# TCC.net
KiCad netlist of a schematic drawn in EAGLE
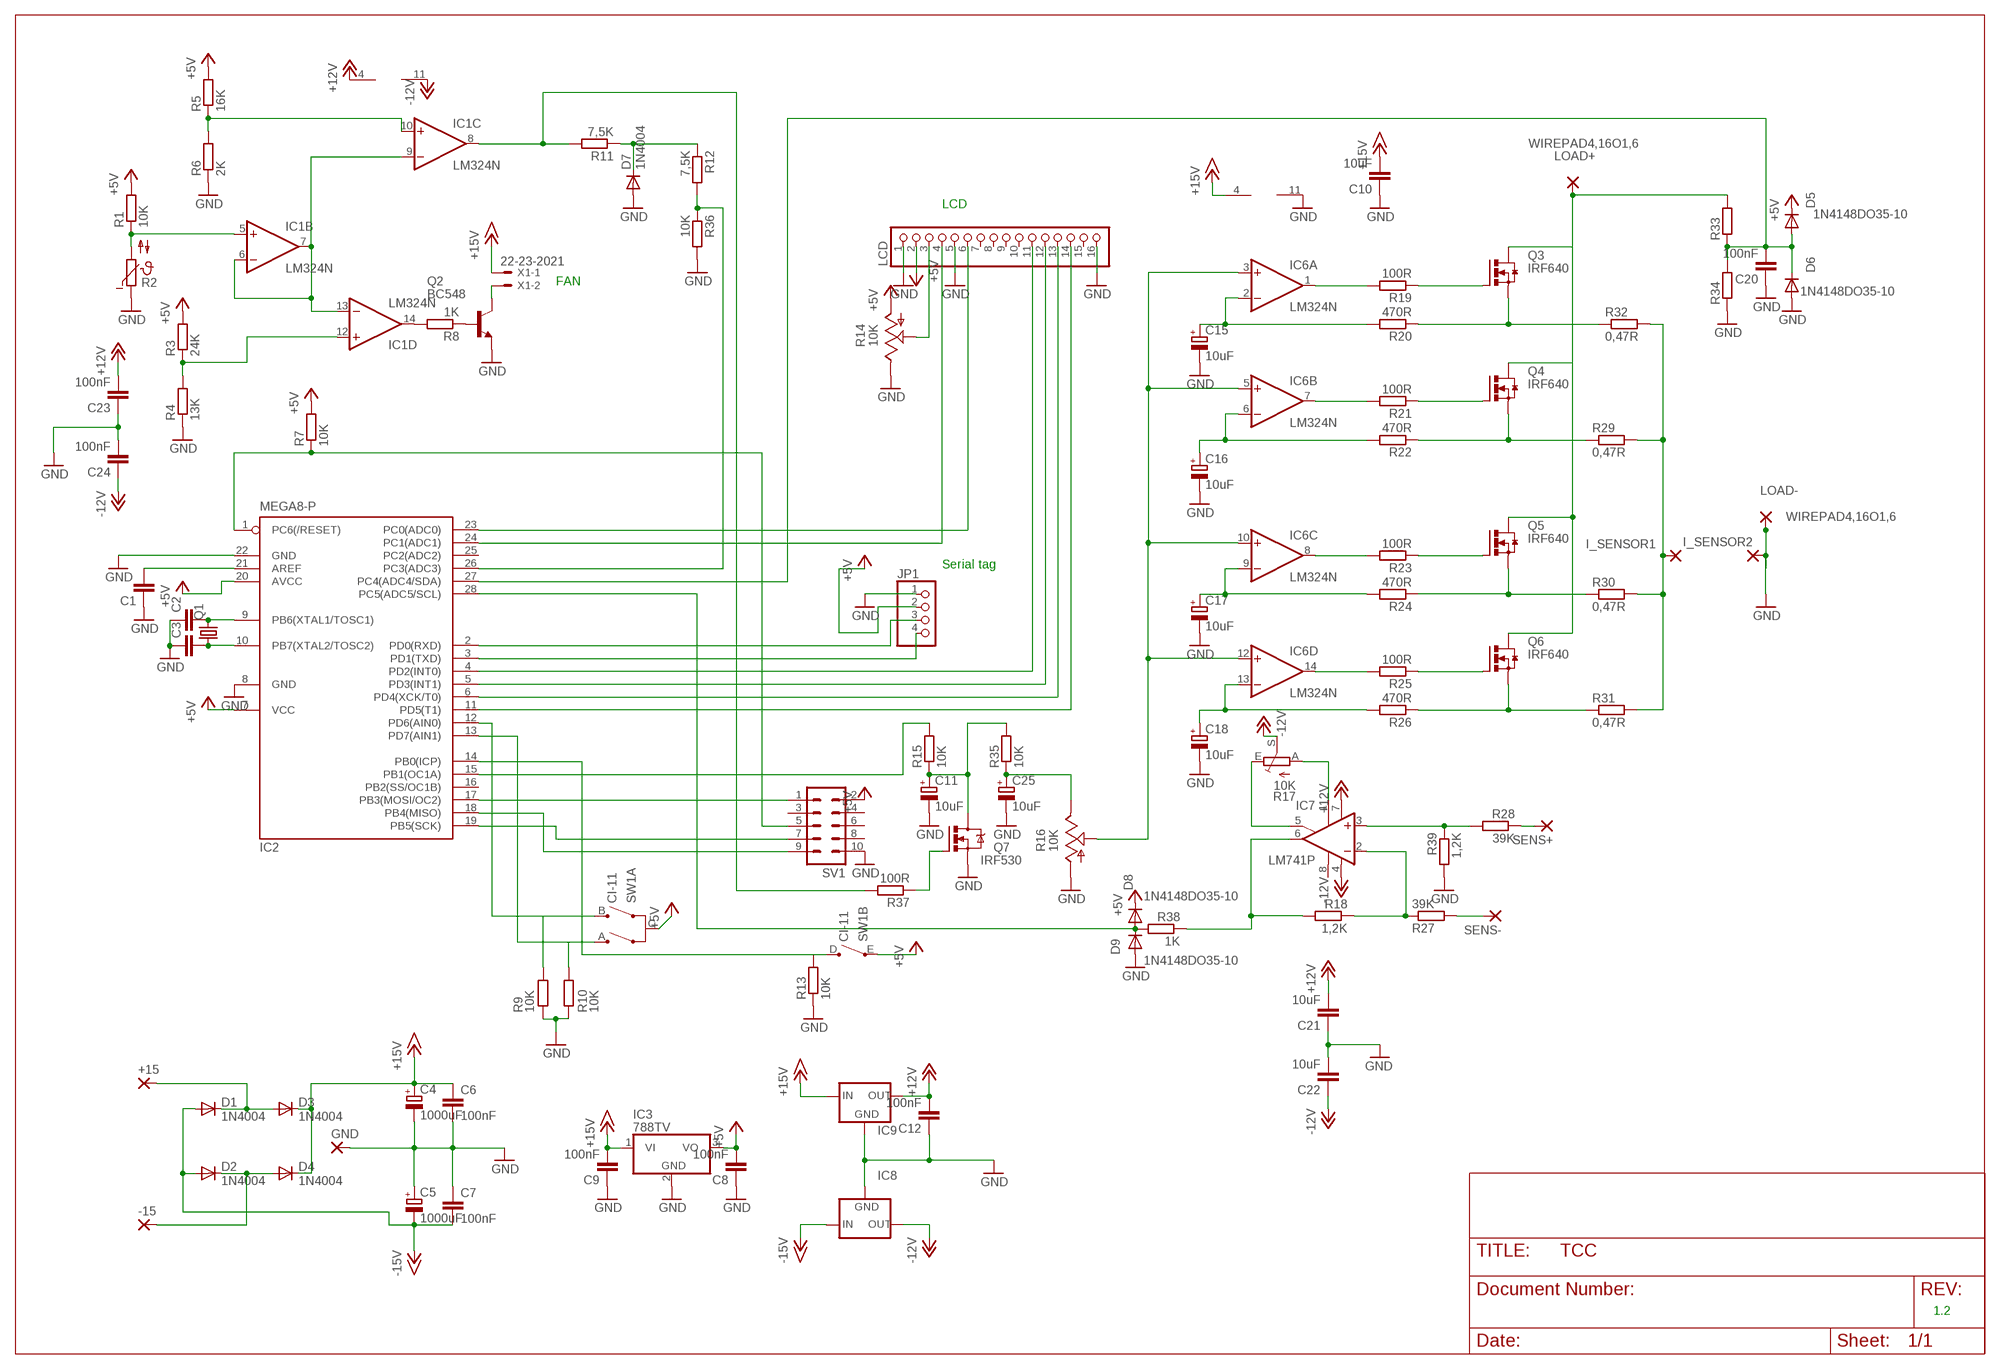
[diagram p0: schematic, sheet 1]

(export (version "E")
  (design (tool "Eeschema 10.0.6"))
  (components
    (comp (ref "+15")
      (value "2,54/0,9")
      (footprint "eagle-import:2,54_0,9")
      (libsource (lib "eagle-import") (part "2,54/0,9"))
    )
    (comp (ref "-15")
      (value "2,54/0,9")
      (footprint "eagle-import:2,54_0,9")
      (libsource (lib "eagle-import") (part "2,54/0,9"))
    )
    (comp (ref "C1")
      (value "C5/2.5")
      (footprint "eagle-import:C5B2.5")
      (libsource (lib "eagle-import") (part "C5/2.5"))
    )
    (comp (ref "C2")
      (value "C5/2.5")
      (footprint "eagle-import:C5B2.5")
      (libsource (lib "eagle-import") (part "C5/2.5"))
    )
    (comp (ref "C3")
      (value "C5/2.5")
      (footprint "eagle-import:C5B2.5")
      (libsource (lib "eagle-import") (part "C5/2.5"))
    )
    (comp (ref "C4")
      (value "1000uF")
      (footprint "eagle-import:E3,5-10")
      (libsource (lib "eagle-import") (part "CPOL-EUE3.5-10"))
    )
    (comp (ref "C5")
      (value "1000uF")
      (footprint "eagle-import:E3,5-10")
      (libsource (lib "eagle-import") (part "CPOL-EUE3.5-10"))
    )
    (comp (ref "C6")
      (value "100nF")
      (footprint "eagle-import:C050-025X075")
      (libsource (lib "eagle-import") (part "C-EU050-025X075"))
    )
    (comp (ref "C7")
      (value "100nF")
      (footprint "eagle-import:C050-025X075")
      (libsource (lib "eagle-import") (part "C-EU050-025X075"))
    )
    (comp (ref "C8")
      (value "100nF")
      (footprint "eagle-import:C5B2.5")
      (libsource (lib "eagle-import") (part "C5/2.5"))
    )
    (comp (ref "C9")
      (value "100nF")
      (footprint "eagle-import:C5B2.5")
      (libsource (lib "eagle-import") (part "C5/2.5"))
    )
    (comp (ref "C10")
      (value "10uF")
      (footprint "eagle-import:C5B2.5")
      (libsource (lib "eagle-import") (part "C5/2.5"))
    )
    (comp (ref "C11")
      (value "10uF")
      (footprint "eagle-import:E2,5-6E")
      (libsource (lib "eagle-import") (part "CPOL-EUE2,5-6E"))
    )
    (comp (ref "C12")
      (value "100nF")
      (footprint "eagle-import:C5B2.5")
      (libsource (lib "eagle-import") (part "C5/2.5"))
    )
    (comp (ref "C15")
      (value "10uF")
      (footprint "eagle-import:E2,5-6E")
      (libsource (lib "eagle-import") (part "CPOL-EUE2,5-6E"))
    )
    (comp (ref "C16")
      (value "10uF")
      (footprint "eagle-import:E2,5-6E")
      (libsource (lib "eagle-import") (part "CPOL-EUE2,5-6E"))
    )
    (comp (ref "C17")
      (value "10uF")
      (footprint "eagle-import:E2,5-6E")
      (libsource (lib "eagle-import") (part "CPOL-EUE2,5-6E"))
    )
    (comp (ref "C18")
      (value "10uF")
      (footprint "eagle-import:E2,5-6E")
      (libsource (lib "eagle-import") (part "CPOL-EUE2,5-6E"))
    )
    (comp (ref "C20")
      (value "100nF")
      (footprint "eagle-import:C5B2.5")
      (libsource (lib "eagle-import") (part "C5/2.5"))
    )
    (comp (ref "C21")
      (value "10uF")
      (footprint "eagle-import:C5B2.5")
      (libsource (lib "eagle-import") (part "C5/2.5"))
    )
    (comp (ref "C22")
      (value "10uF")
      (footprint "eagle-import:C5B2.5")
      (libsource (lib "eagle-import") (part "C5/2.5"))
    )
    (comp (ref "C23")
      (value "100nF")
      (footprint "eagle-import:C5B2.5")
      (libsource (lib "eagle-import") (part "C5/2.5"))
    )
    (comp (ref "C24")
      (value "100nF")
      (footprint "eagle-import:C5B2.5")
      (libsource (lib "eagle-import") (part "C5/2.5"))
    )
    (comp (ref "C25")
      (value "10uF")
      (footprint "eagle-import:E2,5-6E")
      (libsource (lib "eagle-import") (part "CPOL-EUE2,5-6E"))
    )
    (comp (ref "D1")
      (value "1N4004")
      (footprint "eagle-import:DO41-10")
      (libsource (lib "eagle-import") (part "1N4004"))
    )
    (comp (ref "D2")
      (value "1N4004")
      (footprint "eagle-import:DO41-10")
      (libsource (lib "eagle-import") (part "1N4004"))
    )
    (comp (ref "D3")
      (value "1N4004")
      (footprint "eagle-import:DO41-10")
      (libsource (lib "eagle-import") (part "1N4004"))
    )
    (comp (ref "D4")
      (value "1N4004")
      (footprint "eagle-import:DO41-10")
      (libsource (lib "eagle-import") (part "1N4004"))
    )
    (comp (ref "D5")
      (value "1N4148DO35-10")
      (footprint "eagle-import:DO35-10")
      (libsource (lib "eagle-import") (part "1N4148DO35-10"))
    )
    (comp (ref "D6")
      (value "1N4148DO35-10")
      (footprint "eagle-import:DO35-10")
      (libsource (lib "eagle-import") (part "1N4148DO35-10"))
    )
    (comp (ref "D7")
      (value "1N4004")
      (footprint "eagle-import:DO41-10")
      (libsource (lib "eagle-import") (part "1N4004"))
    )
    (comp (ref "D8")
      (value "1N4148DO35-10")
      (footprint "eagle-import:DO35-10")
      (libsource (lib "eagle-import") (part "1N4148DO35-10"))
    )
    (comp (ref "D9")
      (value "1N4148DO35-10")
      (footprint "eagle-import:DO35-10")
      (libsource (lib "eagle-import") (part "1N4148DO35-10"))
    )
    (comp (ref "GND")
      (value "2,54/0,9")
      (footprint "eagle-import:2,54_0,9")
      (libsource (lib "eagle-import") (part "2,54/0,9"))
    )
    (comp (ref "IC1")
      (value "LM324N")
      (footprint "eagle-import:DIL14")
      (libsource (lib "eagle-import") (part "LM324N"))
    )
    (comp (ref "IC2")
      (value "MEGA8-P")
      (footprint "eagle-import:DIL28-3")
      (libsource (lib "eagle-import") (part "MEGA8-P"))
    )
    (comp (ref "IC3")
      (value "788TV")
      (footprint "eagle-import:TO220V")
      (libsource (lib "eagle-import") (part "78TV8"))
    )
    (comp (ref "IC6")
      (value "LM324N")
      (footprint "eagle-import:DIL14")
      (libsource (lib "eagle-import") (part "LM324N"))
    )
    (comp (ref "IC7")
      (value "LM741P")
      (footprint "eagle-import:DIL08")
      (libsource (lib "eagle-import") (part "741PLM"))
    )
    (comp (ref "IC8")
      (value "79XXS")
      (footprint "eagle-import:79XXS")
      (libsource (lib "eagle-import") (part "79XXS"))
    )
    (comp (ref "IC9")
      (value "78XXS")
      (footprint "eagle-import:78XXS")
      (libsource (lib "eagle-import") (part "78XXS"))
    )
    (comp (ref "I_SENSOR1")
      (value "3,17/1,3")
      (footprint "eagle-import:3,17_1,3")
      (libsource (lib "eagle-import") (part "3,17/1,3"))
    )
    (comp (ref "I_SENSOR2")
      (value "3,17/1,3")
      (footprint "eagle-import:3,17_1,3")
      (libsource (lib "eagle-import") (part "3,17/1,3"))
    )
    (comp (ref "JP1")
      (value "PINHD-1X4")
      (footprint "eagle-import:1X04")
      (libsource (lib "eagle-import") (part "PINHD-1X4"))
    )
    (comp (ref "LCD")
      (value "PINHD-1X16")
      (footprint "eagle-import:1X16")
      (libsource (lib "eagle-import") (part "PINHD-1X16"))
    )
    (comp (ref "LOAD+")
      (value "WIREPAD4,16O1,6")
      (footprint "eagle-import:4,16O1,6")
      (libsource (lib "eagle-import") (part "WIREPAD4,16O1,6"))
    )
    (comp (ref "LOAD-")
      (value "WIREPAD4,16O1,6")
      (footprint "eagle-import:4,16O1,6")
      (libsource (lib "eagle-import") (part "WIREPAD4,16O1,6"))
    )
    (comp (ref "Q1")
      (value "CRYSTALHC49S")
      (footprint "eagle-import:HC49_S")
      (libsource (lib "eagle-import") (part "CRYSTALHC49S"))
    )
    (comp (ref "Q2")
      (value "BC548")
      (footprint "eagle-import:TO92-EBC")
      (libsource (lib "eagle-import") (part "BC548"))
    )
    (comp (ref "Q3")
      (value "IRF640")
      (footprint "eagle-import:TO220BH")
      (libsource (lib "eagle-import") (part "IRFI540NPBF"))
    )
    (comp (ref "Q4")
      (value "IRF640")
      (footprint "eagle-import:TO220BH")
      (libsource (lib "eagle-import") (part "IRFI540NPBF"))
    )
    (comp (ref "Q5")
      (value "IRF640")
      (footprint "eagle-import:TO220BH")
      (libsource (lib "eagle-import") (part "IRFI540NPBF"))
    )
    (comp (ref "Q6")
      (value "IRF640")
      (footprint "eagle-import:TO220BH")
      (libsource (lib "eagle-import") (part "IRFI540NPBF"))
    )
    (comp (ref "Q7")
      (value "IRF530")
      (footprint "eagle-import:TO220BV")
      (libsource (lib "eagle-import") (part "IRF530"))
    )
    (comp (ref "R1")
      (value "10K")
      (footprint "eagle-import:0207_12")
      (libsource (lib "eagle-import") (part "resistor_R-EU_0207/12"))
    )
    (comp (ref "R2")
      (value "NTC640")
      (footprint "eagle-import:P640")
      (libsource (lib "eagle-import") (part "NTC640"))
    )
    (comp (ref "R3")
      (value "24K")
      (footprint "eagle-import:0207_10")
      (libsource (lib "eagle-import") (part "resistor_R-EU_0207/10"))
    )
    (comp (ref "R4")
      (value "13K")
      (footprint "eagle-import:0204_7")
      (libsource (lib "eagle-import") (part "resistor_R-EU_0204/7"))
    )
    (comp (ref "R5")
      (value "16K")
      (footprint "eagle-import:0204_7")
      (libsource (lib "eagle-import") (part "resistor_R-EU_0204/7"))
    )
    (comp (ref "R6")
      (value "2K")
      (footprint "eagle-import:0204_7")
      (libsource (lib "eagle-import") (part "resistor_R-EU_0204/7"))
    )
    (comp (ref "R7")
      (value "10K")
      (footprint "eagle-import:0204_7")
      (libsource (lib "eagle-import") (part "resistor_R-EU_0204/7"))
    )
    (comp (ref "R8")
      (value "1K")
      (footprint "eagle-import:0204_7")
      (libsource (lib "eagle-import") (part "resistor_R-EU_0204/7"))
    )
    (comp (ref "R9")
      (value "10K")
      (footprint "eagle-import:0204_7")
      (libsource (lib "eagle-import") (part "R-EU_0204/7"))
    )
    (comp (ref "R10")
      (value "10K")
      (footprint "eagle-import:0204_7")
      (libsource (lib "eagle-import") (part "R-EU_0204/7"))
    )
    (comp (ref "R11")
      (value "7,5K")
      (footprint "eagle-import:0204_7")
      (libsource (lib "eagle-import") (part "resistor_R-EU_0204/7"))
    )
    (comp (ref "R12")
      (value "7,5K")
      (footprint "eagle-import:0204_7")
      (libsource (lib "eagle-import") (part "resistor_R-EU_0204/7"))
    )
    (comp (ref "R13")
      (value "10K")
      (footprint "eagle-import:0207_10")
      (libsource (lib "eagle-import") (part "R-EU_0207/10"))
    )
    (comp (ref "R14")
      (value "10K")
      (footprint "eagle-import:LI10@1")
      (libsource (lib "eagle-import") (part "TRIM_US-LI10"))
    )
    (comp (ref "R15")
      (value "10K")
      (footprint "eagle-import:0204_7")
      (libsource (lib "eagle-import") (part "resistor_R-EU_0204/7"))
    )
    (comp (ref "R16")
      (value "10K")
      (footprint "eagle-import:S64W")
      (libsource (lib "eagle-import") (part "TRIM_US-S64W"))
    )
    (comp (ref "R17")
      (value "10K")
      (footprint "eagle-import:LI10")
      (libsource (lib "eagle-import") (part "TRIM_EU-LI10"))
    )
    (comp (ref "R18")
      (value "1,2K")
      (footprint "eagle-import:0207_10")
      (libsource (lib "eagle-import") (part "R-EU_0207/10"))
    )
    (comp (ref "R19")
      (value "100R")
      (footprint "eagle-import:0207_10")
      (libsource (lib "eagle-import") (part "R-EU_0207/10"))
    )
    (comp (ref "R20")
      (value "470R")
      (footprint "eagle-import:0207_10")
      (libsource (lib "eagle-import") (part "R-EU_0207/10"))
    )
    (comp (ref "R21")
      (value "100R")
      (footprint "eagle-import:0207_15")
      (libsource (lib "eagle-import") (part "R-EU_0207/15"))
    )
    (comp (ref "R22")
      (value "470R")
      (footprint "eagle-import:0207_12")
      (libsource (lib "eagle-import") (part "R-EU_0207/12"))
    )
    (comp (ref "R23")
      (value "100R")
      (footprint "eagle-import:0207_15")
      (libsource (lib "eagle-import") (part "R-EU_0207/15"))
    )
    (comp (ref "R24")
      (value "470R")
      (footprint "eagle-import:0207_10")
      (libsource (lib "eagle-import") (part "R-EU_0207/10"))
    )
    (comp (ref "R25")
      (value "100R")
      (footprint "eagle-import:0207_10")
      (libsource (lib "eagle-import") (part "R-EU_0207/10"))
    )
    (comp (ref "R26")
      (value "470R")
      (footprint "eagle-import:0207_10")
      (libsource (lib "eagle-import") (part "R-EU_0207/10"))
    )
    (comp (ref "R27")
      (value "39K")
      (footprint "eagle-import:0207_10")
      (libsource (lib "eagle-import") (part "R-EU_0207/10"))
    )
    (comp (ref "R28")
      (value "39K")
      (footprint "eagle-import:0204_7")
      (libsource (lib "eagle-import") (part "R-EU_0204/7"))
    )
    (comp (ref "R29")
      (value "0,47R")
      (footprint "eagle-import:VTA56")
      (libsource (lib "eagle-import") (part "R-EU_VTA56"))
    )
    (comp (ref "R30")
      (value "0,47R")
      (footprint "eagle-import:VTA56")
      (libsource (lib "eagle-import") (part "R-EU_VTA56"))
    )
    (comp (ref "R31")
      (value "0,47R")
      (footprint "eagle-import:VTA56")
      (libsource (lib "eagle-import") (part "R-EU_VTA56"))
    )
    (comp (ref "R32")
      (value "0,47R")
      (footprint "eagle-import:VTA56")
      (libsource (lib "eagle-import") (part "R-EU_VTA56"))
    )
    (comp (ref "R33")
      (value "R-EU_0207/15")
      (footprint "eagle-import:0207_15")
      (libsource (lib "eagle-import") (part "R-EU_0207/15"))
    )
    (comp (ref "R34")
      (value "R-EU_0207/10")
      (footprint "eagle-import:0207_10")
      (libsource (lib "eagle-import") (part "R-EU_0207/10"))
    )
    (comp (ref "R35")
      (value "10K")
      (footprint "eagle-import:0204_7")
      (libsource (lib "eagle-import") (part "resistor_R-EU_0204/7"))
    )
    (comp (ref "R36")
      (value "10K")
      (footprint "eagle-import:0204_7")
      (libsource (lib "eagle-import") (part "resistor_R-EU_0204/7"))
    )
    (comp (ref "R37")
      (value "100R")
      (footprint "eagle-import:0204_7")
      (libsource (lib "eagle-import") (part "resistor_R-EU_0204/7"))
    )
    (comp (ref "R38")
      (value "1K")
      (footprint "eagle-import:0207_10")
      (libsource (lib "eagle-import") (part "R-EU_0207/10"))
    )
    (comp (ref "R39")
      (value "1,2K")
      (footprint "eagle-import:0207_10")
      (libsource (lib "eagle-import") (part "R-EU_0207/10"))
    )
    (comp (ref "SENS+")
      (value "2,54/1,1")
      (footprint "eagle-import:2,54_1,1")
      (libsource (lib "eagle-import") (part "2,54/1,1"))
    )
    (comp (ref "SENS-")
      (value "2,54/1,1")
      (footprint "eagle-import:2,54_1,1")
      (libsource (lib "eagle-import") (part "2,54/1,1"))
    )
    (comp (ref "SV1")
      (value "ML10")
      (footprint "eagle-import:ML10")
      (libsource (lib "eagle-import") (part "ML10"))
    )
    (comp (ref "SW1")
      (value "CI-11")
      (footprint "eagle-import:CI-11")
      (libsource (lib "eagle-import") (part "CI-11"))
    )
    (comp (ref "X1")
      (value "22-23-2021")
      (footprint "eagle-import:22-23-2021")
      (fields (field (name "MF") "MOLEX"))
      (libsource (lib "eagle-import") (part "22-23-2021"))
    )
  )
  (nets
    (net (code "1") (name "+5V") (class "Default")
      (node (ref "C8") (pin "2") (pinfunction "2_2") (pintype "passive"))
      (node (ref "D5") (pin "C") (pinfunction "C_C") (pintype "passive"))
      (node (ref "D8") (pin "C") (pinfunction "C_C") (pintype "passive"))
      (node (ref "IC2") (pin "20") (pinfunction "AVCC_20") (pintype "power_in"))
      (node (ref "IC2") (pin "7") (pinfunction "VCC_7") (pintype "power_in"))
      (node (ref "IC3") (pin "3") (pinfunction "VO_3") (pintype "passive"))
      (node (ref "JP1") (pin "2") (pinfunction "2_2") (pintype "passive"))
      (node (ref "LCD") (pin "2") (pinfunction "2_2") (pintype "passive"))
      (node (ref "R1") (pin "2") (pinfunction "2_2") (pintype "passive"))
      (node (ref "R14") (pin "A") (pinfunction "A_A") (pintype "passive"))
      (node (ref "R3") (pin "2") (pinfunction "2_2") (pintype "passive"))
      (node (ref "R5") (pin "2") (pinfunction "2_2") (pintype "passive"))
      (node (ref "R7") (pin "2") (pinfunction "2_2") (pintype "passive"))
      (node (ref "SV1") (pin "2") (pinfunction "2_2") (pintype "passive"))
      (node (ref "SW1") (pin "C") (pinfunction "C_C") (pintype "passive"))
      (node (ref "SW1") (pin "E") (pinfunction "E_E") (pintype "passive"))
    )
    (net (code "2") (name "+12V") (class "Default")
      (node (ref "C12") (pin "2") (pinfunction "2_2") (pintype "passive"))
      (node (ref "C21") (pin "2") (pinfunction "2_2") (pintype "passive"))
      (node (ref "C23") (pin "2") (pinfunction "2_2") (pintype "passive"))
      (node (ref "IC1") (pin "4") (pinfunction "V+_4") (pintype "power_in"))
      (node (ref "IC7") (pin "7") (pinfunction "V+_7") (pintype "power_in"))
      (node (ref "IC9") (pin "OUT") (pinfunction "OUT_OUT") (pintype "passive"))
    )
    (net (code "3") (name "+15V") (class "Default")
      (node (ref "C10") (pin "2") (pinfunction "2_2") (pintype "passive"))
      (node (ref "C4") (pin "+") (pinfunction "+_+") (pintype "passive"))
      (node (ref "C6") (pin "1") (pinfunction "1_1") (pintype "passive"))
      (node (ref "C9") (pin "2") (pinfunction "2_2") (pintype "passive"))
      (node (ref "D3") (pin "C") (pinfunction "C_C") (pintype "passive"))
      (node (ref "D4") (pin "C") (pinfunction "C_C") (pintype "passive"))
      (node (ref "IC3") (pin "1") (pinfunction "VI_1") (pintype "input"))
      (node (ref "IC6") (pin "4") (pinfunction "V+_4") (pintype "power_in"))
      (node (ref "IC9") (pin "IN") (pinfunction "IN_IN") (pintype "input"))
      (node (ref "X1") (pin "1") (pinfunction "S_1") (pintype "passive"))
    )
    (net (code "4") (name "-12V") (class "Default")
      (node (ref "C22") (pin "1") (pinfunction "1_1") (pintype "passive"))
      (node (ref "C24") (pin "1") (pinfunction "1_1") (pintype "passive"))
      (node (ref "IC1") (pin "11") (pinfunction "V-_11") (pintype "power_in"))
      (node (ref "IC7") (pin "4") (pinfunction "V-_4") (pintype "power_in"))
      (node (ref "IC8") (pin "OUT") (pinfunction "OUT_OUT") (pintype "passive"))
      (node (ref "R17") (pin "S") (pinfunction "S_S") (pintype "passive"))
    )
    (net (code "5") (name "-15V") (class "Default")
      (node (ref "C5") (pin "-") (pinfunction "-_-") (pintype "passive"))
      (node (ref "C7") (pin "2") (pinfunction "2_2") (pintype "passive"))
      (node (ref "D1") (pin "A") (pinfunction "A_A") (pintype "passive"))
      (node (ref "D2") (pin "A") (pinfunction "A_A") (pintype "passive"))
      (node (ref "IC8") (pin "IN") (pinfunction "IN_IN") (pintype "input"))
    )
    (net (code "6") (name "GND") (class "Default")
      (node (ref "C1") (pin "1") (pinfunction "1_1") (pintype "passive"))
      (node (ref "C10") (pin "1") (pinfunction "1_1") (pintype "passive"))
      (node (ref "C11") (pin "-") (pinfunction "-_-") (pintype "passive"))
      (node (ref "C12") (pin "1") (pinfunction "1_1") (pintype "passive"))
      (node (ref "C15") (pin "-") (pinfunction "-_-") (pintype "passive"))
      (node (ref "C16") (pin "-") (pinfunction "-_-") (pintype "passive"))
      (node (ref "C17") (pin "-") (pinfunction "-_-") (pintype "passive"))
      (node (ref "C18") (pin "-") (pinfunction "-_-") (pintype "passive"))
      (node (ref "C2") (pin "1") (pinfunction "1_1") (pintype "passive"))
      (node (ref "C20") (pin "1") (pinfunction "1_1") (pintype "passive"))
      (node (ref "C21") (pin "1") (pinfunction "1_1") (pintype "passive"))
      (node (ref "C22") (pin "2") (pinfunction "2_2") (pintype "passive"))
      (node (ref "C23") (pin "1") (pinfunction "1_1") (pintype "passive"))
      (node (ref "C24") (pin "2") (pinfunction "2_2") (pintype "passive"))
      (node (ref "C25") (pin "-") (pinfunction "-_-") (pintype "passive"))
      (node (ref "C3") (pin "1") (pinfunction "1_1") (pintype "passive"))
      (node (ref "C4") (pin "-") (pinfunction "-_-") (pintype "passive"))
      (node (ref "C5") (pin "+") (pinfunction "+_+") (pintype "passive"))
      (node (ref "C6") (pin "2") (pinfunction "2_2") (pintype "passive"))
      (node (ref "C7") (pin "1") (pinfunction "1_1") (pintype "passive"))
      (node (ref "C8") (pin "1") (pinfunction "1_1") (pintype "passive"))
      (node (ref "C9") (pin "1") (pinfunction "1_1") (pintype "passive"))
      (node (ref "D6") (pin "A") (pinfunction "A_A") (pintype "passive"))
      (node (ref "D7") (pin "A") (pinfunction "A_A") (pintype "passive"))
      (node (ref "D9") (pin "A") (pinfunction "A_A") (pintype "passive"))
      (node (ref "GND") (pin "1") (pinfunction "P_1") (pintype "passive"))
      (node (ref "IC2") (pin "22") (pinfunction "GND_22") (pintype "power_in"))
      (node (ref "IC2") (pin "8") (pinfunction "GND_8") (pintype "power_in"))
      (node (ref "IC3") (pin "2") (pinfunction "GND_2") (pintype "passive"))
      (node (ref "IC6") (pin "11") (pinfunction "V-_11") (pintype "power_in"))
      (node (ref "IC8") (pin "GND") (pinfunction "GND_GND") (pintype "input"))
      (node (ref "IC9") (pin "GND") (pinfunction "GND_GND") (pintype "input"))
      (node (ref "I_SENSOR2") (pin "1") (pinfunction "P_1") (pintype "passive"))
      (node (ref "JP1") (pin "1") (pinfunction "1_1") (pintype "passive"))
      (node (ref "LCD") (pin "1") (pinfunction "1_1") (pintype "passive"))
      (node (ref "LCD") (pin "16") (pinfunction "16_16") (pintype "passive"))
      (node (ref "LCD") (pin "5") (pinfunction "5_5") (pintype "passive"))
      (node (ref "LOAD-") (pin "1") (pinfunction "P_1") (pintype "passive"))
      (node (ref "Q2") (pin "E") (pinfunction "E_E") (pintype "passive"))
      (node (ref "Q7") (pin "S") (pinfunction "S_S") (pintype "passive"))
      (node (ref "R10") (pin "1") (pinfunction "1_1") (pintype "passive"))
      (node (ref "R13") (pin "1") (pinfunction "1_1") (pintype "passive"))
      (node (ref "R14") (pin "E") (pinfunction "E_E") (pintype "passive"))
      (node (ref "R16") (pin "A") (pinfunction "A_A") (pintype "passive"))
      (node (ref "R2") (pin "1") (pinfunction "1_1") (pintype "passive"))
      (node (ref "R34") (pin "1") (pinfunction "1_1") (pintype "passive"))
      (node (ref "R36") (pin "2") (pinfunction "2_2") (pintype "passive"))
      (node (ref "R39") (pin "2") (pinfunction "2_2") (pintype "passive"))
      (node (ref "R4") (pin "1") (pinfunction "1_1") (pintype "passive"))
      (node (ref "R6") (pin "1") (pinfunction "1_1") (pintype "passive"))
      (node (ref "R9") (pin "1") (pinfunction "1_1") (pintype "passive"))
      (node (ref "SV1") (pin "10") (pinfunction "10_10") (pintype "passive"))
    )
    (net (code "7") (name "Net-(+15-P)") (class "Default")
      (node (ref "+15") (pin "1") (pinfunction "P_1") (pintype "passive"))
      (node (ref "D1") (pin "C") (pinfunction "C_C") (pintype "passive"))
      (node (ref "D3") (pin "A") (pinfunction "A_A") (pintype "passive"))
    )
    (net (code "8") (name "Net-(-15-P)") (class "Default")
      (node (ref "-15") (pin "1") (pinfunction "P_1") (pintype "passive"))
      (node (ref "D2") (pin "C") (pinfunction "C_C") (pintype "passive"))
      (node (ref "D4") (pin "A") (pinfunction "A_A") (pintype "passive"))
    )
    (net (code "9") (name "Net-(C11-Pad+)") (class "Default")
      (node (ref "C11") (pin "+") (pinfunction "+_+") (pintype "passive"))
      (node (ref "Q7") (pin "D") (pinfunction "D_D") (pintype "passive"))
      (node (ref "R15") (pin "1") (pinfunction "1_1") (pintype "passive"))
      (node (ref "R35") (pin "2") (pinfunction "2_2") (pintype "passive"))
    )
    (net (code "10") (name "Net-(C25-Pad+)") (class "Default")
      (node (ref "C25") (pin "+") (pinfunction "+_+") (pintype "passive"))
      (node (ref "R16") (pin "E") (pinfunction "E_E") (pintype "passive"))
      (node (ref "R35") (pin "1") (pinfunction "1_1") (pintype "passive"))
    )
    (net (code "11") (name "Net-(D7-PadC)") (class "Default")
      (node (ref "D7") (pin "C") (pinfunction "C_C") (pintype "passive"))
      (node (ref "R11") (pin "1") (pinfunction "1_1") (pintype "passive"))
      (node (ref "R12") (pin "1") (pinfunction "1_1") (pintype "passive"))
    )
    (net (code "12") (name "Net-(IC1B-+IN)") (class "Default")
      (node (ref "IC1") (pin "5") (pinfunction "+IN_5") (pintype "input"))
      (node (ref "R1") (pin "1") (pinfunction "1_1") (pintype "passive"))
      (node (ref "R2") (pin "2") (pinfunction "2_2") (pintype "passive"))
    )
    (net (code "13") (name "Net-(IC1B--IN)") (class "Default")
      (node (ref "IC1") (pin "13") (pinfunction "-IN_13") (pintype "input"))
      (node (ref "IC1") (pin "6") (pinfunction "-IN_6") (pintype "input"))
      (node (ref "IC1") (pin "7") (pinfunction "OUT_7") (pintype "output"))
      (node (ref "IC1") (pin "9") (pinfunction "-IN_9") (pintype "input"))
    )
    (net (code "14") (name "Net-(IC1C-+IN)") (class "Default")
      (node (ref "IC1") (pin "10") (pinfunction "+IN_10") (pintype "input"))
      (node (ref "R5") (pin "1") (pinfunction "1_1") (pintype "passive"))
      (node (ref "R6") (pin "2") (pinfunction "2_2") (pintype "passive"))
    )
    (net (code "15") (name "Net-(IC1C-OUT)") (class "Default")
      (node (ref "IC1") (pin "8") (pinfunction "OUT_8") (pintype "output"))
      (node (ref "R11") (pin "2") (pinfunction "2_2") (pintype "passive"))
      (node (ref "R37") (pin "2") (pinfunction "2_2") (pintype "passive"))
    )
    (net (code "16") (name "Net-(IC1D-+IN)") (class "Default")
      (node (ref "IC1") (pin "12") (pinfunction "+IN_12") (pintype "input"))
      (node (ref "R3") (pin "1") (pinfunction "1_1") (pintype "passive"))
      (node (ref "R4") (pin "2") (pinfunction "2_2") (pintype "passive"))
    )
    (net (code "17") (name "Net-(IC1D-OUT)") (class "Default")
      (node (ref "IC1") (pin "14") (pinfunction "OUT_14") (pintype "output"))
      (node (ref "R8") (pin "2") (pinfunction "2_2") (pintype "passive"))
    )
    (net (code "18") (name "Net-(IC2-AREF)") (class "Default")
      (node (ref "C1") (pin "2") (pinfunction "2_2") (pintype "passive"))
      (node (ref "IC2") (pin "21") (pinfunction "AREF_21") (pintype "passive"))
    )
    (net (code "19") (name "Net-(IC2-PB0(ICP))") (class "Default")
      (node (ref "IC2") (pin "14") (pinfunction "PB0(ICP)_14") (pintype "bidirectional"))
      (node (ref "R13") (pin "2") (pinfunction "2_2") (pintype "passive"))
      (node (ref "SW1") (pin "D") (pinfunction "D_D") (pintype "passive"))
    )
    (net (code "20") (name "Net-(IC2-PB1(OC1A))") (class "Default")
      (node (ref "IC2") (pin "15") (pinfunction "PB1(OC1A)_15") (pintype "bidirectional"))
      (node (ref "R15") (pin "2") (pinfunction "2_2") (pintype "passive"))
    )
    (net (code "21") (name "Net-(IC2-PB3(MOSI{slash}OC2))") (class "Default")
      (node (ref "IC2") (pin "17") (pinfunction "PB3(MOSI/OC2)_17") (pintype "bidirectional"))
      (node (ref "SV1") (pin "1") (pinfunction "1_1") (pintype "passive"))
    )
    (net (code "22") (name "Net-(IC2-PB4(MISO))") (class "Default")
      (node (ref "IC2") (pin "18") (pinfunction "PB4(MISO)_18") (pintype "bidirectional"))
      (node (ref "SV1") (pin "9") (pinfunction "9_9") (pintype "passive"))
    )
    (net (code "23") (name "Net-(IC2-PB5(SCK))") (class "Default")
      (node (ref "IC2") (pin "19") (pinfunction "PB5(SCK)_19") (pintype "bidirectional"))
      (node (ref "SV1") (pin "7") (pinfunction "7_7") (pintype "passive"))
    )
    (net (code "24") (name "Net-(IC2-PB6(XTAL1{slash}TOSC1))") (class "Default")
      (node (ref "C2") (pin "2") (pinfunction "2_2") (pintype "passive"))
      (node (ref "IC2") (pin "9") (pinfunction "PB6(XTAL1/TOSC1)_9") (pintype "bidirectional"))
      (node (ref "Q1") (pin "2") (pinfunction "2_2") (pintype "passive"))
    )
    (net (code "25") (name "Net-(IC2-PB7(XTAL2{slash}TOSC2))") (class "Default")
      (node (ref "C3") (pin "2") (pinfunction "2_2") (pintype "passive"))
      (node (ref "IC2") (pin "10") (pinfunction "PB7(XTAL2/TOSC2)_10") (pintype "bidirectional"))
      (node (ref "Q1") (pin "1") (pinfunction "1_1") (pintype "passive"))
    )
    (net (code "26") (name "Net-(IC2-PC0(ADC0))") (class "Default")
      (node (ref "IC2") (pin "23") (pinfunction "PC0(ADC0)_23") (pintype "bidirectional"))
      (node (ref "LCD") (pin "6") (pinfunction "6_6") (pintype "passive"))
    )
    (net (code "27") (name "Net-(IC2-PC1(ADC1))") (class "Default")
      (node (ref "IC2") (pin "24") (pinfunction "PC1(ADC1)_24") (pintype "bidirectional"))
      (node (ref "LCD") (pin "4") (pinfunction "4_4") (pintype "passive"))
    )
    (net (code "28") (name "Net-(IC2-PC3(ADC3))") (class "Default")
      (node (ref "IC2") (pin "26") (pinfunction "PC3(ADC3)_26") (pintype "bidirectional"))
      (node (ref "R12") (pin "2") (pinfunction "2_2") (pintype "passive"))
      (node (ref "R36") (pin "1") (pinfunction "1_1") (pintype "passive"))
    )
    (net (code "29") (name "Net-(IC2-PC4(ADC4{slash}SDA))") (class "Default")
      (node (ref "C20") (pin "2") (pinfunction "2_2") (pintype "passive"))
      (node (ref "D5") (pin "A") (pinfunction "A_A") (pintype "passive"))
      (node (ref "D6") (pin "C") (pinfunction "C_C") (pintype "passive"))
      (node (ref "IC2") (pin "27") (pinfunction "PC4(ADC4/SDA)_27") (pintype "bidirectional"))
      (node (ref "R33") (pin "1") (pinfunction "1_1") (pintype "passive"))
      (node (ref "R34") (pin "2") (pinfunction "2_2") (pintype "passive"))
    )
    (net (code "30") (name "Net-(IC2-PC5(ADC5{slash}SCL))") (class "Default")
      (node (ref "D8") (pin "A") (pinfunction "A_A") (pintype "passive"))
      (node (ref "D9") (pin "C") (pinfunction "C_C") (pintype "passive"))
      (node (ref "IC2") (pin "28") (pinfunction "PC5(ADC5/SCL)_28") (pintype "bidirectional"))
      (node (ref "R38") (pin "2") (pinfunction "2_2") (pintype "passive"))
    )
    (net (code "31") (name "Net-(IC2-PC6({slash}RESET))") (class "Default")
      (node (ref "IC2") (pin "1") (pinfunction "PC6(/RESET)_1") (pintype "bidirectional"))
      (node (ref "R7") (pin "1") (pinfunction "1_1") (pintype "passive"))
      (node (ref "SV1") (pin "5") (pinfunction "5_5") (pintype "passive"))
    )
    (net (code "32") (name "Net-(IC2-PD0(RXD))") (class "Default")
      (node (ref "IC2") (pin "2") (pinfunction "PD0(RXD)_2") (pintype "bidirectional"))
      (node (ref "JP1") (pin "3") (pinfunction "3_3") (pintype "passive"))
    )
    (net (code "33") (name "Net-(IC2-PD1(TXD))") (class "Default")
      (node (ref "IC2") (pin "3") (pinfunction "PD1(TXD)_3") (pintype "bidirectional"))
      (node (ref "JP1") (pin "4") (pinfunction "4_4") (pintype "passive"))
    )
    (net (code "34") (name "Net-(IC2-PD2(INT0))") (class "Default")
      (node (ref "IC2") (pin "4") (pinfunction "PD2(INT0)_4") (pintype "bidirectional"))
      (node (ref "LCD") (pin "11") (pinfunction "11_11") (pintype "passive"))
    )
    (net (code "35") (name "Net-(IC2-PD3(INT1))") (class "Default")
      (node (ref "IC2") (pin "5") (pinfunction "PD3(INT1)_5") (pintype "bidirectional"))
      (node (ref "LCD") (pin "12") (pinfunction "12_12") (pintype "passive"))
    )
    (net (code "36") (name "Net-(IC2-PD4(XCK{slash}T0))") (class "Default")
      (node (ref "IC2") (pin "6") (pinfunction "PD4(XCK/T0)_6") (pintype "bidirectional"))
      (node (ref "LCD") (pin "13") (pinfunction "13_13") (pintype "passive"))
    )
    (net (code "37") (name "Net-(IC2-PD5(T1))") (class "Default")
      (node (ref "IC2") (pin "11") (pinfunction "PD5(T1)_11") (pintype "bidirectional"))
      (node (ref "LCD") (pin "14") (pinfunction "14_14") (pintype "passive"))
    )
    (net (code "38") (name "Net-(IC2-PD6(AIN0))") (class "Default")
      (node (ref "IC2") (pin "12") (pinfunction "PD6(AIN0)_12") (pintype "bidirectional"))
      (node (ref "R9") (pin "2") (pinfunction "2_2") (pintype "passive"))
      (node (ref "SW1") (pin "B") (pinfunction "B_B") (pintype "passive"))
    )
    (net (code "39") (name "Net-(IC2-PD7(AIN1))") (class "Default")
      (node (ref "IC2") (pin "13") (pinfunction "PD7(AIN1)_13") (pintype "bidirectional"))
      (node (ref "R10") (pin "2") (pinfunction "2_2") (pintype "passive"))
      (node (ref "SW1") (pin "A") (pinfunction "A_A") (pintype "passive"))
    )
    (net (code "40") (name "Net-(IC6A-+IN)") (class "Default")
      (node (ref "IC6") (pin "10") (pinfunction "+IN_10") (pintype "input"))
      (node (ref "IC6") (pin "12") (pinfunction "+IN_12") (pintype "input"))
      (node (ref "IC6") (pin "3") (pinfunction "+IN_3") (pintype "input"))
      (node (ref "IC6") (pin "5") (pinfunction "+IN_5") (pintype "input"))
      (node (ref "R16") (pin "S") (pinfunction "S_S") (pintype "passive"))
    )
    (net (code "41") (name "Net-(IC6A--IN)") (class "Default")
      (node (ref "C15") (pin "+") (pinfunction "+_+") (pintype "passive"))
      (node (ref "IC6") (pin "2") (pinfunction "-IN_2") (pintype "input"))
      (node (ref "R20") (pin "2") (pinfunction "2_2") (pintype "passive"))
    )
    (net (code "42") (name "Net-(IC6A-OUT)") (class "Default")
      (node (ref "IC6") (pin "1") (pinfunction "OUT_1") (pintype "output"))
      (node (ref "R19") (pin "2") (pinfunction "2_2") (pintype "passive"))
    )
    (net (code "43") (name "Net-(IC6B--IN)") (class "Default")
      (node (ref "C16") (pin "+") (pinfunction "+_+") (pintype "passive"))
      (node (ref "IC6") (pin "6") (pinfunction "-IN_6") (pintype "input"))
      (node (ref "R22") (pin "2") (pinfunction "2_2") (pintype "passive"))
    )
    (net (code "44") (name "Net-(IC6B-OUT)") (class "Default")
      (node (ref "IC6") (pin "7") (pinfunction "OUT_7") (pintype "output"))
      (node (ref "R21") (pin "2") (pinfunction "2_2") (pintype "passive"))
    )
    (net (code "45") (name "Net-(IC6C--IN)") (class "Default")
      (node (ref "C17") (pin "+") (pinfunction "+_+") (pintype "passive"))
      (node (ref "IC6") (pin "9") (pinfunction "-IN_9") (pintype "input"))
      (node (ref "R24") (pin "2") (pinfunction "2_2") (pintype "passive"))
    )
    (net (code "46") (name "Net-(IC6C-OUT)") (class "Default")
      (node (ref "IC6") (pin "8") (pinfunction "OUT_8") (pintype "output"))
      (node (ref "R23") (pin "2") (pinfunction "2_2") (pintype "passive"))
    )
    (net (code "47") (name "Net-(IC6D--IN)") (class "Default")
      (node (ref "C18") (pin "+") (pinfunction "+_+") (pintype "passive"))
      (node (ref "IC6") (pin "13") (pinfunction "-IN_13") (pintype "input"))
      (node (ref "R26") (pin "2") (pinfunction "2_2") (pintype "passive"))
    )
    (net (code "48") (name "Net-(IC6D-OUT)") (class "Default")
      (node (ref "IC6") (pin "14") (pinfunction "OUT_14") (pintype "output"))
      (node (ref "R25") (pin "2") (pinfunction "2_2") (pintype "passive"))
    )
    (net (code "49") (name "Net-(IC7-+IN)") (class "Default")
      (node (ref "IC7") (pin "3") (pinfunction "+IN_3") (pintype "input"))
      (node (ref "R28") (pin "2") (pinfunction "2_2") (pintype "passive"))
      (node (ref "R39") (pin "1") (pinfunction "1_1") (pintype "passive"))
    )
    (net (code "50") (name "Net-(IC7--IN)") (class "Default")
      (node (ref "IC7") (pin "2") (pinfunction "-IN_2") (pintype "input"))
      (node (ref "R18") (pin "1") (pinfunction "1_1") (pintype "passive"))
      (node (ref "R27") (pin "1") (pinfunction "1_1") (pintype "passive"))
    )
    (net (code "51") (name "Net-(IC7-ON1)") (class "Default")
      (node (ref "IC7") (pin "1") (pinfunction "ON1_1") (pintype "passive"))
      (node (ref "R17") (pin "A") (pinfunction "A_A") (pintype "passive"))
    )
    (net (code "52") (name "Net-(IC7-ON2)") (class "Default")
      (node (ref "IC7") (pin "5") (pinfunction "ON2_5") (pintype "passive"))
      (node (ref "R17") (pin "E") (pinfunction "E_E") (pintype "passive"))
    )
    (net (code "53") (name "Net-(IC7-OUT)") (class "Default")
      (node (ref "IC7") (pin "6") (pinfunction "OUT_6") (pintype "output"))
      (node (ref "R18") (pin "2") (pinfunction "2_2") (pintype "passive"))
      (node (ref "R38") (pin "1") (pinfunction "1_1") (pintype "passive"))
    )
    (net (code "54") (name "Net-(I_SENSOR1-P)") (class "Default")
      (node (ref "I_SENSOR1") (pin "1") (pinfunction "P_1") (pintype "passive"))
      (node (ref "R29") (pin "2") (pinfunction "2_2") (pintype "passive"))
      (node (ref "R30") (pin "2") (pinfunction "2_2") (pintype "passive"))
      (node (ref "R31") (pin "2") (pinfunction "2_2") (pintype "passive"))
      (node (ref "R32") (pin "2") (pinfunction "2_2") (pintype "passive"))
    )
    (net (code "55") (name "Net-(LCD-Pad3)") (class "Default")
      (node (ref "LCD") (pin "3") (pinfunction "3_3") (pintype "passive"))
      (node (ref "R14") (pin "S") (pinfunction "S_S") (pintype "passive"))
    )
    (net (code "56") (name "Net-(LOAD+-P)") (class "Default")
      (node (ref "LOAD+") (pin "1") (pinfunction "P_1") (pintype "passive"))
      (node (ref "Q3") (pin "D") (pinfunction "D_D") (pintype "passive"))
      (node (ref "Q4") (pin "D") (pinfunction "D_D") (pintype "passive"))
      (node (ref "Q5") (pin "D") (pinfunction "D_D") (pintype "passive"))
      (node (ref "Q6") (pin "D") (pinfunction "D_D") (pintype "passive"))
      (node (ref "R33") (pin "2") (pinfunction "2_2") (pintype "passive"))
    )
    (net (code "57") (name "Net-(Q2-PadB)") (class "Default")
      (node (ref "Q2") (pin "B") (pinfunction "B_B") (pintype "passive"))
      (node (ref "R8") (pin "1") (pinfunction "1_1") (pintype "passive"))
    )
    (net (code "58") (name "Net-(Q3-PadG)") (class "Default")
      (node (ref "Q3") (pin "G") (pinfunction "G_G") (pintype "passive"))
      (node (ref "R19") (pin "1") (pinfunction "1_1") (pintype "passive"))
    )
    (net (code "59") (name "Net-(Q3-PadS)") (class "Default")
      (node (ref "Q3") (pin "S") (pinfunction "S_S") (pintype "passive"))
      (node (ref "R20") (pin "1") (pinfunction "1_1") (pintype "passive"))
      (node (ref "R32") (pin "1") (pinfunction "1_1") (pintype "passive"))
    )
    (net (code "60") (name "Net-(Q4-PadG)") (class "Default")
      (node (ref "Q4") (pin "G") (pinfunction "G_G") (pintype "passive"))
      (node (ref "R21") (pin "1") (pinfunction "1_1") (pintype "passive"))
    )
    (net (code "61") (name "Net-(Q4-PadS)") (class "Default")
      (node (ref "Q4") (pin "S") (pinfunction "S_S") (pintype "passive"))
      (node (ref "R22") (pin "1") (pinfunction "1_1") (pintype "passive"))
      (node (ref "R29") (pin "1") (pinfunction "1_1") (pintype "passive"))
    )
    (net (code "62") (name "Net-(Q5-PadG)") (class "Default")
      (node (ref "Q5") (pin "G") (pinfunction "G_G") (pintype "passive"))
      (node (ref "R23") (pin "1") (pinfunction "1_1") (pintype "passive"))
    )
    (net (code "63") (name "Net-(Q5-PadS)") (class "Default")
      (node (ref "Q5") (pin "S") (pinfunction "S_S") (pintype "passive"))
      (node (ref "R24") (pin "1") (pinfunction "1_1") (pintype "passive"))
      (node (ref "R30") (pin "1") (pinfunction "1_1") (pintype "passive"))
    )
    (net (code "64") (name "Net-(Q6-PadG)") (class "Default")
      (node (ref "Q6") (pin "G") (pinfunction "G_G") (pintype "passive"))
      (node (ref "R25") (pin "1") (pinfunction "1_1") (pintype "passive"))
    )
    (net (code "65") (name "Net-(Q6-PadS)") (class "Default")
      (node (ref "Q6") (pin "S") (pinfunction "S_S") (pintype "passive"))
      (node (ref "R26") (pin "1") (pinfunction "1_1") (pintype "passive"))
      (node (ref "R31") (pin "1") (pinfunction "1_1") (pintype "passive"))
    )
    (net (code "66") (name "Net-(Q7-PadG)") (class "Default")
      (node (ref "Q7") (pin "G") (pinfunction "G_G") (pintype "passive"))
      (node (ref "R37") (pin "1") (pinfunction "1_1") (pintype "passive"))
    )
    (net (code "67") (name "Net-(SENS+-P)") (class "Default")
      (node (ref "R28") (pin "1") (pinfunction "1_1") (pintype "passive"))
      (node (ref "SENS+") (pin "1") (pinfunction "P_1") (pintype "passive"))
    )
    (net (code "68") (name "Net-(SENS--P)") (class "Default")
      (node (ref "R27") (pin "2") (pinfunction "2_2") (pintype "passive"))
      (node (ref "SENS-") (pin "1") (pinfunction "P_1") (pintype "passive"))
    )
    (net (code "69") (name "Net-(X1B-S)") (class "Default")
      (node (ref "Q2") (pin "C") (pinfunction "C_C") (pintype "passive"))
      (node (ref "X1") (pin "2") (pinfunction "S_2") (pintype "passive"))
    )
    (net (code "70") (name "unconnected-(IC2-PB2(SS{slash}OC1B)-Pad16)") (class "Default")
      (node (ref "IC2") (pin "16") (pinfunction "PB2(SS/OC1B)_16") (pintype "bidirectional"))
    )
    (net (code "71") (name "unconnected-(IC2-PC2(ADC2)-Pad25)") (class "Default")
      (node (ref "IC2") (pin "25") (pinfunction "PC2(ADC2)_25") (pintype "bidirectional"))
    )
    (net (code "72") (name "unconnected-(IC7-OPT-Pad8)") (class "Default")
      (node (ref "IC7") (pin "8") (pinfunction "OPT_8") (pintype "passive"))
    )
    (net (code "73") (name "unconnected-(LCD-Pad7)") (class "Default")
      (node (ref "LCD") (pin "7") (pinfunction "7_7") (pintype "passive"))
    )
    (net (code "74") (name "unconnected-(LCD-Pad8)") (class "Default")
      (node (ref "LCD") (pin "8") (pinfunction "8_8") (pintype "passive"))
    )
    (net (code "75") (name "unconnected-(LCD-Pad9)") (class "Default")
      (node (ref "LCD") (pin "9") (pinfunction "9_9") (pintype "passive"))
    )
    (net (code "76") (name "unconnected-(LCD-Pad10)") (class "Default")
      (node (ref "LCD") (pin "10") (pinfunction "10_10") (pintype "passive"))
    )
    (net (code "77") (name "unconnected-(LCD-Pad15)") (class "Default")
      (node (ref "LCD") (pin "15") (pinfunction "15_15") (pintype "passive"))
    )
    (net (code "78") (name "unconnected-(SV1-Pad3)") (class "Default")
      (node (ref "SV1") (pin "3") (pinfunction "3_3") (pintype "passive"))
    )
    (net (code "79") (name "unconnected-(SV1-Pad4)") (class "Default")
      (node (ref "SV1") (pin "4") (pinfunction "4_4") (pintype "passive"))
    )
    (net (code "80") (name "unconnected-(SV1-Pad6)") (class "Default")
      (node (ref "SV1") (pin "6") (pinfunction "6_6") (pintype "passive"))
    )
    (net (code "81") (name "unconnected-(SV1-Pad8)") (class "Default")
      (node (ref "SV1") (pin "8") (pinfunction "8_8") (pintype "passive"))
    )
  )
)
